# Conectores.net
KiCad netlist of a schematic drawn in Altium Designer
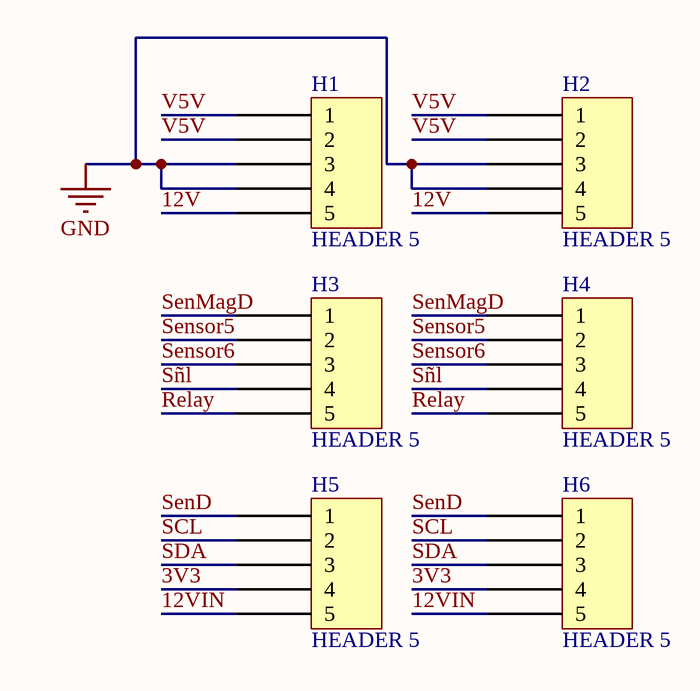
[diagram p0: Conectores.SchDoc]

(export (version "E")
  (design (tool "Eeschema 10.0.6"))
  (components
    (comp (ref "H1") (value "HEADER 5") (footprint "HEADER5") (libsource (lib "seguintII") (part "HEADER 5")))
    (comp (ref "H2") (value "HEADER 5") (footprint "HEADER5") (libsource (lib "seguintII") (part "HEADER 5")))
    (comp (ref "H3") (value "HEADER 5") (footprint "HEADER5") (libsource (lib "seguintII") (part "HEADER 5")))
    (comp (ref "H4") (value "HEADER 5") (footprint "HEADER5") (libsource (lib "seguintII") (part "HEADER 5")))
    (comp (ref "H5") (value "HEADER 5") (footprint "HEADER5") (libsource (lib "seguintII") (part "HEADER 5")))
    (comp (ref "H6") (value "HEADER 5") (footprint "HEADER5") (libsource (lib "seguintII") (part "HEADER 5")))
  )
  (nets
    (net (code "1") (name "/3V3") (class "Default")
      (node (ref "H5") (pin "4") (pinfunction "4_4") (pintype "passive"))
      (node (ref "H6") (pin "4") (pinfunction "4_4") (pintype "passive"))
    )
    (net (code "2") (name "/12V") (class "Default")
      (node (ref "H1") (pin "5") (pinfunction "5_5") (pintype "passive"))
      (node (ref "H2") (pin "5") (pinfunction "5_5") (pintype "passive"))
    )
    (net (code "3") (name "/12VIN") (class "Default")
      (node (ref "H5") (pin "5") (pinfunction "5_5") (pintype "passive"))
      (node (ref "H6") (pin "5") (pinfunction "5_5") (pintype "passive"))
    )
    (net (code "4") (name "/Relay") (class "Default")
      (node (ref "H3") (pin "5") (pinfunction "5_5") (pintype "passive"))
      (node (ref "H4") (pin "5") (pinfunction "5_5") (pintype "passive"))
    )
    (net (code "5") (name "/SCL") (class "Default")
      (node (ref "H5") (pin "2") (pinfunction "2_2") (pintype "passive"))
      (node (ref "H6") (pin "2") (pinfunction "2_2") (pintype "passive"))
    )
    (net (code "6") (name "/SDA") (class "Default")
      (node (ref "H5") (pin "3") (pinfunction "3_3") (pintype "passive"))
      (node (ref "H6") (pin "3") (pinfunction "3_3") (pintype "passive"))
    )
    (net (code "7") (name "/SenD") (class "Default")
      (node (ref "H5") (pin "1") (pinfunction "1_1") (pintype "passive"))
      (node (ref "H6") (pin "1") (pinfunction "1_1") (pintype "passive"))
    )
    (net (code "8") (name "/SenMagD") (class "Default")
      (node (ref "H3") (pin "1") (pinfunction "1_1") (pintype "passive"))
      (node (ref "H4") (pin "1") (pinfunction "1_1") (pintype "passive"))
    )
    (net (code "9") (name "/Sensor5") (class "Default")
      (node (ref "H3") (pin "2") (pinfunction "2_2") (pintype "passive"))
      (node (ref "H4") (pin "2") (pinfunction "2_2") (pintype "passive"))
    )
    (net (code "10") (name "/Sensor6") (class "Default")
      (node (ref "H3") (pin "3") (pinfunction "3_3") (pintype "passive"))
      (node (ref "H4") (pin "3") (pinfunction "3_3") (pintype "passive"))
    )
    (net (code "11") (name "/Sñl") (class "Default")
      (node (ref "H3") (pin "4") (pinfunction "4_4") (pintype "passive"))
      (node (ref "H4") (pin "4") (pinfunction "4_4") (pintype "passive"))
    )
    (net (code "12") (name "/V5V") (class "Default")
      (node (ref "H1") (pin "1") (pinfunction "1_1") (pintype "passive"))
      (node (ref "H1") (pin "2") (pinfunction "2_2") (pintype "passive"))
      (node (ref "H2") (pin "1") (pinfunction "1_1") (pintype "passive"))
      (node (ref "H2") (pin "2") (pinfunction "2_2") (pintype "passive"))
    )
    (net (code "13") (name "GND") (class "Default")
      (node (ref "H1") (pin "3") (pinfunction "3_3") (pintype "passive"))
      (node (ref "H1") (pin "4") (pinfunction "4_4") (pintype "passive"))
      (node (ref "H2") (pin "3") (pinfunction "3_3") (pintype "passive"))
      (node (ref "H2") (pin "4") (pinfunction "4_4") (pintype "passive"))
    )
  )
)
